# 5V_Converter.net
KiCad netlist of a schematic drawn in Altium Designer
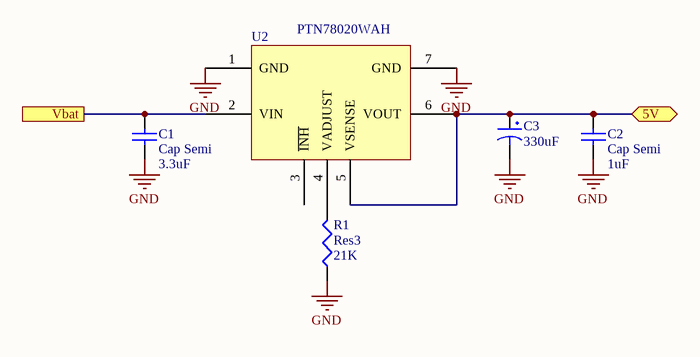
[diagram p0: 5V_Converter.SchDoc]

(export (version "E")
  (design (tool "Eeschema 10.0.6"))
  (components
    (comp (ref "C1")
      (value "Cap Semi")
      (footprint "C1206")
      (description "Capacitor (Semiconductor SIM Model)")
      (fields (field (name "ALTIUM_VALUE") "3.3uF") (field (name "PUBLISHER") "Altium Limited"))
      (libsource (lib "Miscellaneous Devices") (part "Cap Semi"))
    )
    (comp (ref "C2")
      (value "Cap Semi")
      (footprint "C1206")
      (description "Capacitor (Semiconductor SIM Model)")
      (fields (field (name "ALTIUM_VALUE") "1uF") (field (name "PUBLISHER") "Altium Limited"))
      (libsource (lib "Miscellaneous Devices") (part "Cap Semi"))
    )
    (comp (ref "C3")
      (value "330uF")
      (footprint "PCVxxxxxMCLxGS")
      (description "CAP ALUM POLY 390UF 20% 25V SMD")
      (libsource (lib "Power_Embedded_Board_Library") (part "PCV1E391MCL2GS"))
    )
    (comp (ref "R1")
      (value "Res3")
      (footprint "J1-0603")
      (description "Resistor")
      (fields (field (name "ALTIUM_VALUE") "21K") (field (name "PUBLISHER") "Altium Limited"))
      (libsource (lib "Miscellaneous Devices") (part "Res3"))
    )
    (comp (ref "U2")
      (value "PTN78020WAH")
      (footprint "PTN78020WAH")
      (description "6A DC DC Converter")
      (libsource (lib "Power_Embedded_Board_Library") (part "PTN78020WAH"))
    )
  )
  (nets
    (net (code "1") (name "/5V") (class "Default")
      (node (ref "C2") (pin "2") (pinfunction "2_2") (pintype "passive"))
      (node (ref "C3") (pin "1") (pinfunction "1_1") (pintype "passive"))
      (node (ref "U2") (pin "5") (pinfunction "VSENSE_5") (pintype "passive"))
      (node (ref "U2") (pin "6") (pinfunction "VOUT_6") (pintype "passive"))
    )
    (net (code "2") (name "/Vbat") (class "Default")
      (node (ref "C1") (pin "2") (pinfunction "2_2") (pintype "passive"))
      (node (ref "U2") (pin "2") (pinfunction "VIN_2") (pintype "passive"))
    )
    (net (code "3") (name "GND") (class "Default")
      (node (ref "C1") (pin "1") (pinfunction "1_1") (pintype "passive"))
      (node (ref "C2") (pin "1") (pinfunction "1_1") (pintype "passive"))
      (node (ref "C3") (pin "2") (pinfunction "2_2") (pintype "passive"))
      (node (ref "R1") (pin "1") (pinfunction "1_1") (pintype "passive"))
      (node (ref "U2") (pin "1") (pinfunction "GND_1") (pintype "passive"))
      (node (ref "U2") (pin "7") (pinfunction "GND_7") (pintype "passive"))
    )
    (net (code "4") (name "Net-(U2-VADJUST)") (class "Default")
      (node (ref "R1") (pin "2") (pinfunction "2_2") (pintype "passive"))
      (node (ref "U2") (pin "4") (pinfunction "VADJUST_4") (pintype "passive"))
    )
    (net (code "5") (name "unconnected-(U2-~{INH}-Pad3)") (class "Default")
      (node (ref "U2") (pin "3") (pinfunction "~{INH}_3") (pintype "passive"))
    )
  )
)
